# Power.net
KiCad netlist of a schematic drawn in Altium Designer
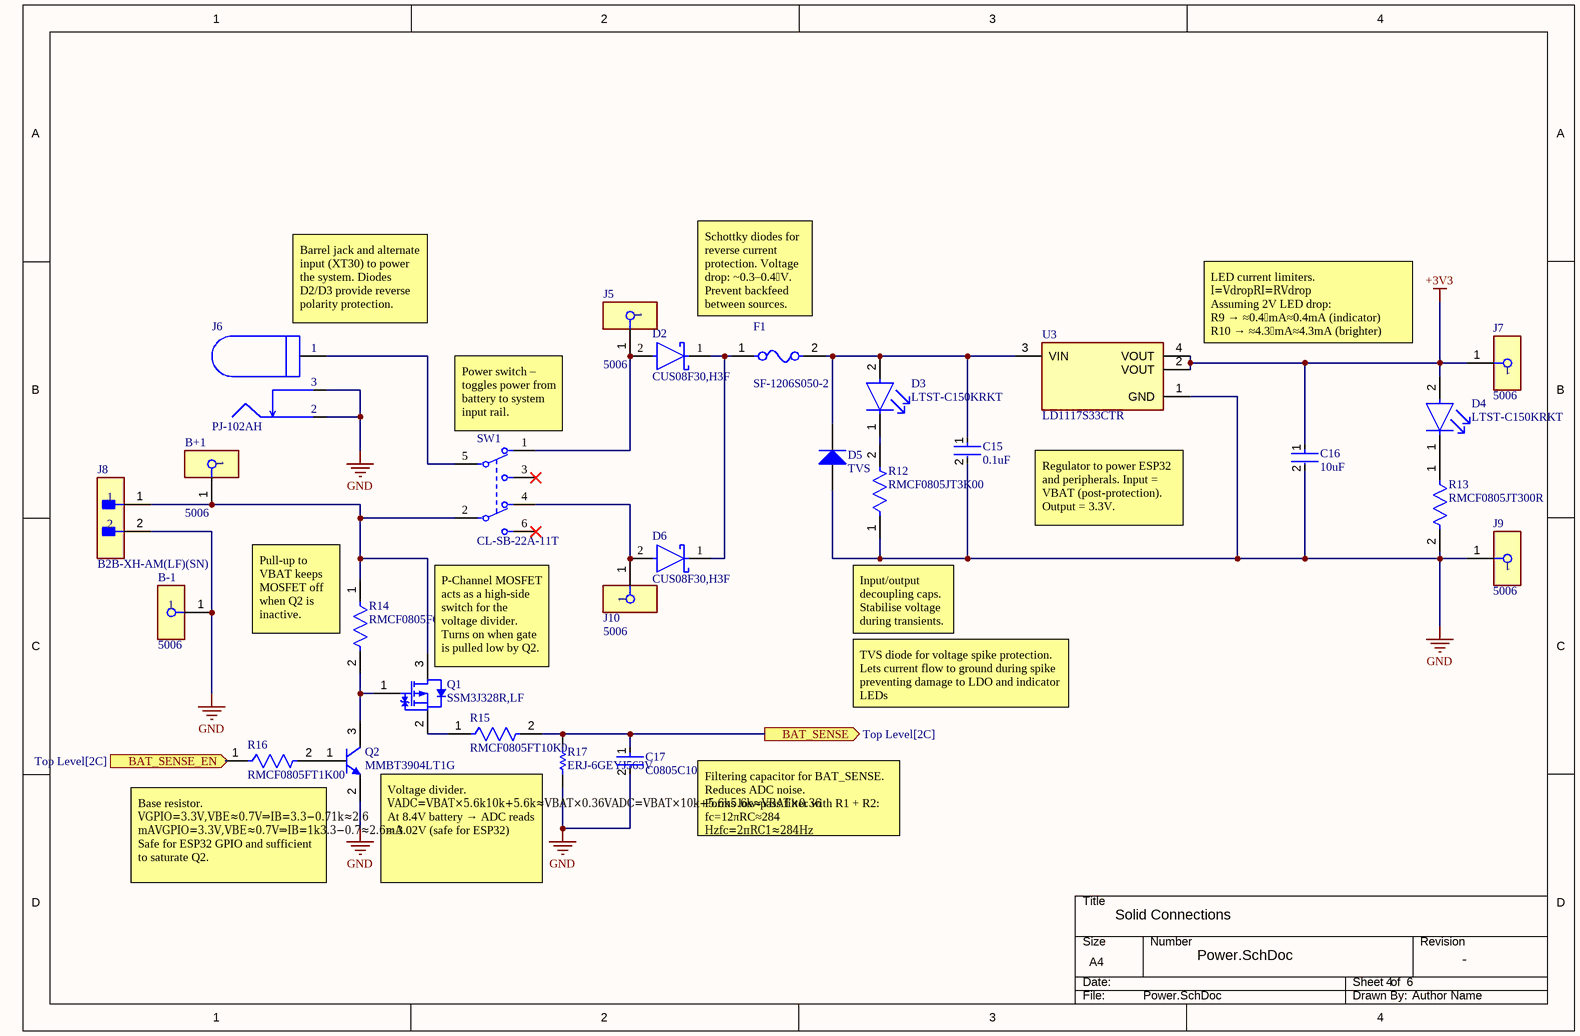
[diagram p0: Power.SchDoc]

(export (version "E")
  (design (tool "Eeschema 10.0.6"))
  (components
    (comp (ref "B+1")
      (value "5006")
      (footprint "FP-5006-MFG")
      (description "PC TEST POINT COMPACT BLACK")
      (libsource (lib "") (part "98815daf2f2c152b0c43f5ab9800df6_1"))
    )
    (comp (ref "B-1")
      (value "5006")
      (footprint "FP-5006-MFG")
      (description "PC TEST POINT COMPACT BLACK")
      (libsource (lib "Altium Content Vault") (part "98815daf2f2c152b0c43f5ab9800df6"))
    )
    (comp (ref "C15")
      (value "0.1uF")
      (footprint "FP-C0805C-DN-MFG")
      (description "CAP CER 0.1UF 50V X7R 0805")
      (fields
        (field (name "OCTOPART") "https://octopart.com/c0805c104j5ractu-kemet-104634")
        (field (name "MANUFACTURER") "KEMET")
      )
      (libsource (lib "Altium Content Vault") (part "b4654b650e69147ec39a6b967a45e02"))
    )
    (comp (ref "C16")
      (value "10uF")
      (footprint "FP-C0805C106J8RACAUTO-MFG")
      (description "CAP CER 10UF 10V X7R 0805")
      (fields (field (name "TOLERANCE") "5%"))
      (libsource (lib "Altium Content Vault") (part "02cd4be3c70576c341d710602a673aa"))
    )
    (comp (ref "C17")
      (value "C0805C103J5RAC7210")
      (footprint "FP-C0805C-DN-MFG")
      (description "CAP CER SMD 0805 .01UF X7R 5% 50")
      (fields
        (field (name "MANUFACTURER") "KEMET")
        (field (name "OCTOPART") "https://octopart.com/c0805c103j5rac7210-kemet-3921106")
      )
      (libsource (lib "Altium Content Vault") (part "b4654b650e69147ec39a6b967a45e02"))
    )
    (comp (ref "D2")
      (value "CUS08F30,H3F")
      (footprint "FP-USC-MFG")
      (description "CUS08F30,H3F Rectifier Diode, Schottky, 1 Phase, 1 Element, 0.8A, 30V V(RRM), Silicon")
      (libsource (lib "Altium Content Vault") (part "c1678fac7984e62e0809fbf79c06691"))
    )
    (comp (ref "D3")
      (value "LTST-C150KRKT")
      (footprint "FP-LTST-C150KRKT-MFG")
      (description "LED RED CLEAR 1206 SMD")
      (libsource (lib "Altium Content Vault") (part "8706943c75ba83719d021d2fdc84c58"))
    )
    (comp (ref "D4")
      (value "LTST-C150KRKT")
      (footprint "FP-LTST-C150KRKT-MFG")
      (description "LED RED CLEAR 1206 SMD")
      (libsource (lib "Altium Content Vault") (part "8706943c75ba83719d021d2fdc84c58"))
    )
    (comp (ref "D5")
      (value "TVS")
      (footprint "VISH-DO-214AC-2_L")
      (fields
        (field (name "PARTNUMBER") "SMAJ10A-E3/61")
        (field (name "MANUFACTURER") "Vishay Semiconductor")
      )
      (libsource (lib "Altium Content Vault") (part "VISH-K1A2-2"))
    )
    (comp (ref "D6")
      (value "CUS08F30,H3F")
      (footprint "FP-USC-MFG")
      (description "CUS08F30,H3F Rectifier Diode, Schottky, 1 Phase, 1 Element, 0.8A, 30V V(RRM), Silicon")
      (libsource (lib "Altium Content Vault") (part "c1678fac7984e62e0809fbf79c06691"))
    )
    (comp (ref "F1")
      (value "SF-1206S050-2")
      (footprint "FP-SF-1206S-MFG")
      (description "FUSE BOARD MNT 500MA 63VDC 1206")
      (fields
        (field (name "MANUFACTURER") "Bourns")
        (field (name "OCTOPART") "https://octopart.com/sf-1206s050-2-bourns-8398336")
      )
      (libsource (lib "Altium Content Vault") (part "5bcf9b9f640e542cf0359d10258e979"))
    )
    (comp (ref "J5")
      (value "5006")
      (footprint "FP-5006-MFG")
      (description "PC TEST POINT COMPACT BLACK")
      (libsource (lib "") (part "98815daf2f2c152b0c43f5ab9800df6_1"))
    )
    (comp (ref "J6")
      (value "PJ-102AH")
      (footprint "CON Barrel PJ-102AH")
      (description "Power Barrel Con, 2.0mm ID, 5.5mm OD, 5A")
      (fields (field (name "MANUFACTURER") "CUI Devices"))
      (libsource (lib "Student_Schlib_41070") (part "CON PWR PJ-102AH"))
    )
    (comp (ref "J7")
      (value "5006")
      (footprint "FP-5006-MFG")
      (description "PC TEST POINT COMPACT BLACK")
      (libsource (lib "") (part "98815daf2f2c152b0c43f5ab9800df6_3"))
    )
    (comp (ref "J8")
      (value "B2B-XH-AM(LF)(SN)")
      (footprint "FP-B2B-XH-AM_LF_SN-MFG")
      (description "CONN HEADER VERT 2POS 2.5MM")
      (libsource (lib "Altium Content Vault") (part "3bc925449376181038e59eaffc5286c"))
    )
    (comp (ref "J9")
      (value "5006")
      (footprint "FP-5006-MFG")
      (description "PC TEST POINT COMPACT BLACK")
      (libsource (lib "") (part "98815daf2f2c152b0c43f5ab9800df6_3"))
    )
    (comp (ref "J10")
      (value "5006")
      (footprint "FP-5006-MFG")
      (description "PC TEST POINT COMPACT BLACK")
      (libsource (lib "") (part "98815daf2f2c152b0c43f5ab9800df6_2"))
    )
    (comp (ref "Q1")
      (value "SSM3J328R,LF")
      (footprint "TOSH-SOT-23F_V")
      (fields (field (name "MANUFACTURER") "Toshiba"))
      (libsource (lib "Altium Content Vault") (part "PEMOS-GSD-3_C"))
    )
    (comp (ref "Q2")
      (value "MMBT3904LT1G")
      (footprint "ONSC-SOT-23-3-318-08_V")
      (description "General Purpose Transistor, NPN Silicon, 3-Pin SOT-23, Pb-Free, Tape and Reel")
      (fields (field (name "MANUFACTURER") "On Semiconductor"))
      (libsource (lib "Altium Content Vault") (part "ONSC-NPN-B1E2C3-3"))
    )
    (comp (ref "R12")
      (value "RMCF0805JT3K00")
      (footprint "FP-RMCF0805-IPC_C")
      (description "3kΩ ±5% 0.125W 0805 Thick Film Chip Resistor AEC-Q200 compliant")
      (fields (field (name "TOLERANCE") "5%"))
      (libsource (lib "Altium Content Vault") (part "1029c3af85768c4190bb7ad29bc67b5"))
    )
    (comp (ref "R13")
      (value "RMCF0805JT300R")
      (footprint "FP-RMCF0805-IPC_B")
      (description "300Ω ±5% 0.125W 0805 Thick Film Chip Resistor AEC-Q200 compliant")
      (fields (field (name "TOLERANCE") "5%"))
      (libsource (lib "Altium Content Vault") (part "1029c3af85768c4190bb7ad29bc67b5"))
    )
    (comp (ref "R14")
      (value "RMCF0805FG100K")
      (footprint "FP-RMCF0805-IPC_C")
      (description "100kΩ ±1% 0.125W 0805 Thick Film Chip Resistor AEC-Q200 compliant")
      (fields (field (name "TOLERANCE") "1%"))
      (libsource (lib "Altium Content Vault") (part "1029c3af85768c4190bb7ad29bc67b5"))
    )
    (comp (ref "R15")
      (value "RMCF0805FT10K0")
      (footprint "FP-RMCF0805-MFG")
      (description "RES 10K OHM 1% 1/8W 0805")
      (fields (field (name "TOLERANCE") "1%"))
      (libsource (lib "Altium Content Vault") (part "1029c3af85768c4190bb7ad29bc67b5"))
    )
    (comp (ref "R16")
      (value "RMCF0805FT1K00")
      (footprint "FP-RMCF0805-IPC_C")
      (description "1kΩ ±1% 0.125W 0805 Thick Film Chip Resistor AEC-Q200 compliant")
      (fields (field (name "TOLERANCE") "1%"))
      (libsource (lib "Altium Content Vault") (part "1029c3af85768c4190bb7ad29bc67b5"))
    )
    (comp (ref "R17")
      (value "ERJ-6GEYJ563V")
      (footprint "RESC2013X70X40ML20T20")
      (fields (field (name "MANUFACTURER") "Panasonic"))
      (libsource (lib "Altium Content Vault") (part "RES"))
    )
    (comp (ref "SW1")
      (value "CL-SB-22A-11T")
      (footprint "FP-CL-SB-22A-11T-MFG")
      (description "SWITCH SLIDE DPDT 200MA 12V")
      (libsource (lib "Altium Content Vault") (part "dfebaf3e7062c737515d8702d298b44"))
    )
    (comp (ref "U3")
      (value "LD1117S33CTR")
      (footprint "FP-SOT-223-0046067_14-MFG")
      (description "IC REG LINEAR 3.3V 800MA SOT223")
      (libsource (lib "Altium Content Vault") (part "7818869c5c16ceab15634627166a29d"))
    )
  )
  (nets
    (net (code "1") (name "+3V3") (class "Default")
      (node (ref "C16") (pin "1") (pinfunction "1_1") (pintype "passive"))
      (node (ref "D4") (pin "2") (pinfunction "A_2") (pintype "passive"))
      (node (ref "J7") (pin "1") (pinfunction "1_1") (pintype "passive"))
      (node (ref "U3") (pin "2") (pinfunction "VOUT_2") (pintype "power_in"))
      (node (ref "U3") (pin "4") (pinfunction "VOUT_4") (pintype "power_in"))
    )
    (net (code "2") (name "/BAT_SENSE") (class "Default")
      (node (ref "C17") (pin "1") (pinfunction "1_1") (pintype "passive"))
      (node (ref "R15") (pin "2") (pinfunction "2_2") (pintype "passive"))
      (node (ref "R17") (pin "2") (pinfunction "2_2") (pintype "passive"))
    )
    (net (code "3") (name "/BAT_SENSE_EN") (class "Default")
      (node (ref "R16") (pin "1") (pinfunction "1_1") (pintype "passive"))
    )
    (net (code "4") (name "GND") (class "Default")
      (node (ref "B-1") (pin "1") (pinfunction "1_1") (pintype "passive"))
      (node (ref "C15") (pin "2") (pinfunction "2_2") (pintype "passive"))
      (node (ref "C16") (pin "2") (pinfunction "2_2") (pintype "passive"))
      (node (ref "C17") (pin "2") (pinfunction "2_2") (pintype "passive"))
      (node (ref "D5") (pin "2") (pinfunction "A_2") (pintype "passive"))
      (node (ref "J6") (pin "2") (pinfunction "2_2") (pintype "passive"))
      (node (ref "J6") (pin "3") (pinfunction "3_3") (pintype "passive"))
      (node (ref "J8") (pin "2") (pinfunction "2_2") (pintype "passive"))
      (node (ref "J9") (pin "1") (pinfunction "1_1") (pintype "passive"))
      (node (ref "Q2") (pin "2") (pinfunction "E_2") (pintype "passive"))
      (node (ref "R12") (pin "1") (pinfunction "1_1") (pintype "passive"))
      (node (ref "R13") (pin "2") (pinfunction "2_2") (pintype "passive"))
      (node (ref "R17") (pin "1") (pinfunction "1_1") (pintype "passive"))
      (node (ref "U3") (pin "1") (pinfunction "GND_1") (pintype "power_in"))
    )
    (net (code "5") (name "Net-(D2-A)") (class "Default")
      (node (ref "D2") (pin "2") (pinfunction "A_2") (pintype "passive"))
      (node (ref "J5") (pin "1") (pinfunction "1_1") (pintype "passive"))
      (node (ref "SW1") (pin "1") (pinfunction "1_1") (pintype "passive"))
    )
    (net (code "6") (name "Net-(D2-C)") (class "Default")
      (node (ref "D2") (pin "1") (pinfunction "C_1") (pintype "passive"))
      (node (ref "D6") (pin "1") (pinfunction "C_1") (pintype "passive"))
      (node (ref "F1") (pin "1") (pinfunction "1_1") (pintype "passive"))
    )
    (net (code "7") (name "Net-(D3-A)") (class "Default")
      (node (ref "C15") (pin "1") (pinfunction "1_1") (pintype "passive"))
      (node (ref "D3") (pin "2") (pinfunction "A_2") (pintype "passive"))
      (node (ref "D5") (pin "1") (pinfunction "K_1") (pintype "passive"))
      (node (ref "F1") (pin "2") (pinfunction "2_2") (pintype "passive"))
      (node (ref "U3") (pin "3") (pinfunction "VIN_3") (pintype "power_in"))
    )
    (net (code "8") (name "Net-(D3-C)") (class "Default")
      (node (ref "D3") (pin "1") (pinfunction "C_1") (pintype "passive"))
      (node (ref "R12") (pin "2") (pinfunction "2_2") (pintype "passive"))
    )
    (net (code "9") (name "Net-(D4-C)") (class "Default")
      (node (ref "D4") (pin "1") (pinfunction "C_1") (pintype "passive"))
      (node (ref "R13") (pin "1") (pinfunction "1_1") (pintype "passive"))
    )
    (net (code "10") (name "Net-(D6-A)") (class "Default")
      (node (ref "D6") (pin "2") (pinfunction "A_2") (pintype "passive"))
      (node (ref "J10") (pin "1") (pinfunction "1_1") (pintype "passive"))
      (node (ref "SW1") (pin "4") (pinfunction "4_4") (pintype "passive"))
    )
    (net (code "11") (name "Net-(J6-Pad1)") (class "Default")
      (node (ref "J6") (pin "1") (pinfunction "1_1") (pintype "passive"))
      (node (ref "SW1") (pin "5") (pinfunction "5_5") (pintype "passive"))
    )
    (net (code "12") (name "Net-(Q1-D)") (class "Default")
      (node (ref "B+1") (pin "1") (pinfunction "1_1") (pintype "passive"))
      (node (ref "J8") (pin "1") (pinfunction "1_1") (pintype "passive"))
      (node (ref "Q1") (pin "3") (pinfunction "D_3") (pintype "passive"))
      (node (ref "R14") (pin "1") (pinfunction "1_1") (pintype "passive"))
      (node (ref "SW1") (pin "2") (pinfunction "2_2") (pintype "passive"))
    )
    (net (code "13") (name "Net-(Q1-G)") (class "Default")
      (node (ref "Q1") (pin "1") (pinfunction "G_1") (pintype "passive"))
      (node (ref "Q2") (pin "3") (pinfunction "C_3") (pintype "passive"))
      (node (ref "R14") (pin "2") (pinfunction "2_2") (pintype "passive"))
    )
    (net (code "14") (name "Net-(Q1-S)") (class "Default")
      (node (ref "Q1") (pin "2") (pinfunction "S_2") (pintype "passive"))
      (node (ref "R15") (pin "1") (pinfunction "1_1") (pintype "passive"))
    )
    (net (code "15") (name "Net-(Q2-B)") (class "Default")
      (node (ref "Q2") (pin "1") (pinfunction "B_1") (pintype "passive"))
      (node (ref "R16") (pin "2") (pinfunction "2_2") (pintype "passive"))
    )
    (net (code "16") (name "unconnected-(SW1-Pad3)") (class "Default")
      (node (ref "SW1") (pin "3") (pinfunction "3_3") (pintype "passive+no_connect"))
    )
    (net (code "17") (name "unconnected-(SW1-Pad6)") (class "Default")
      (node (ref "SW1") (pin "6") (pinfunction "6_6") (pintype "passive+no_connect"))
    )
  )
)
